# bms3_1.net
KiCad netlist of a schematic drawn in EAGLE
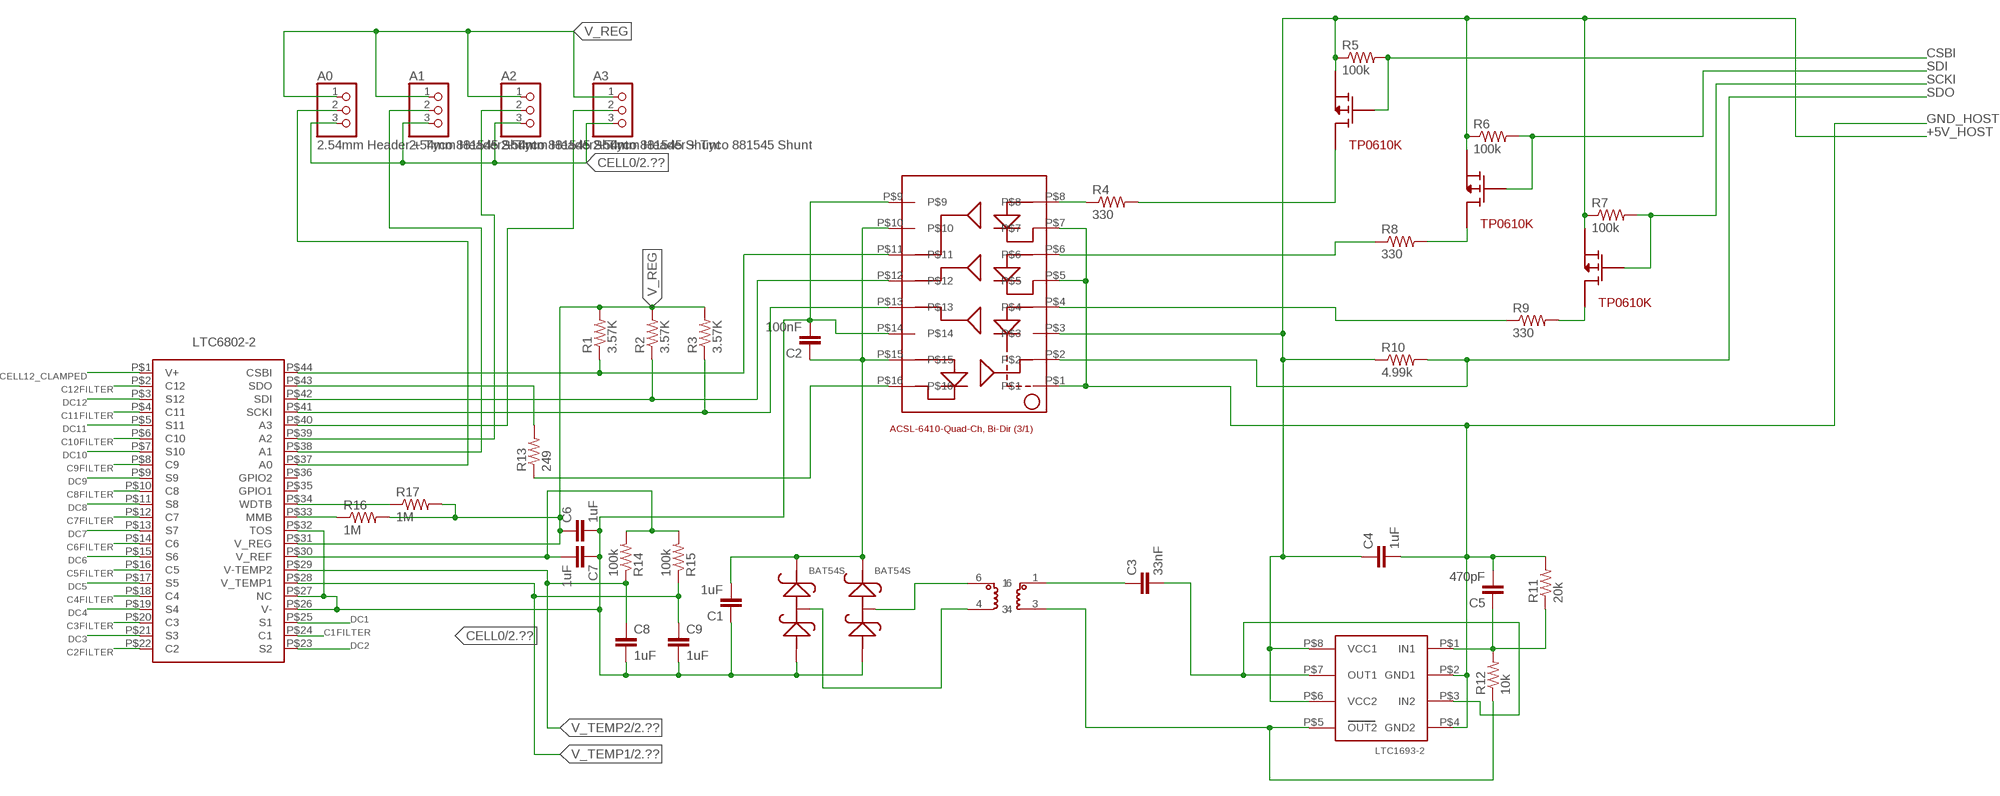
[diagram p0: schematic, sheet 1]
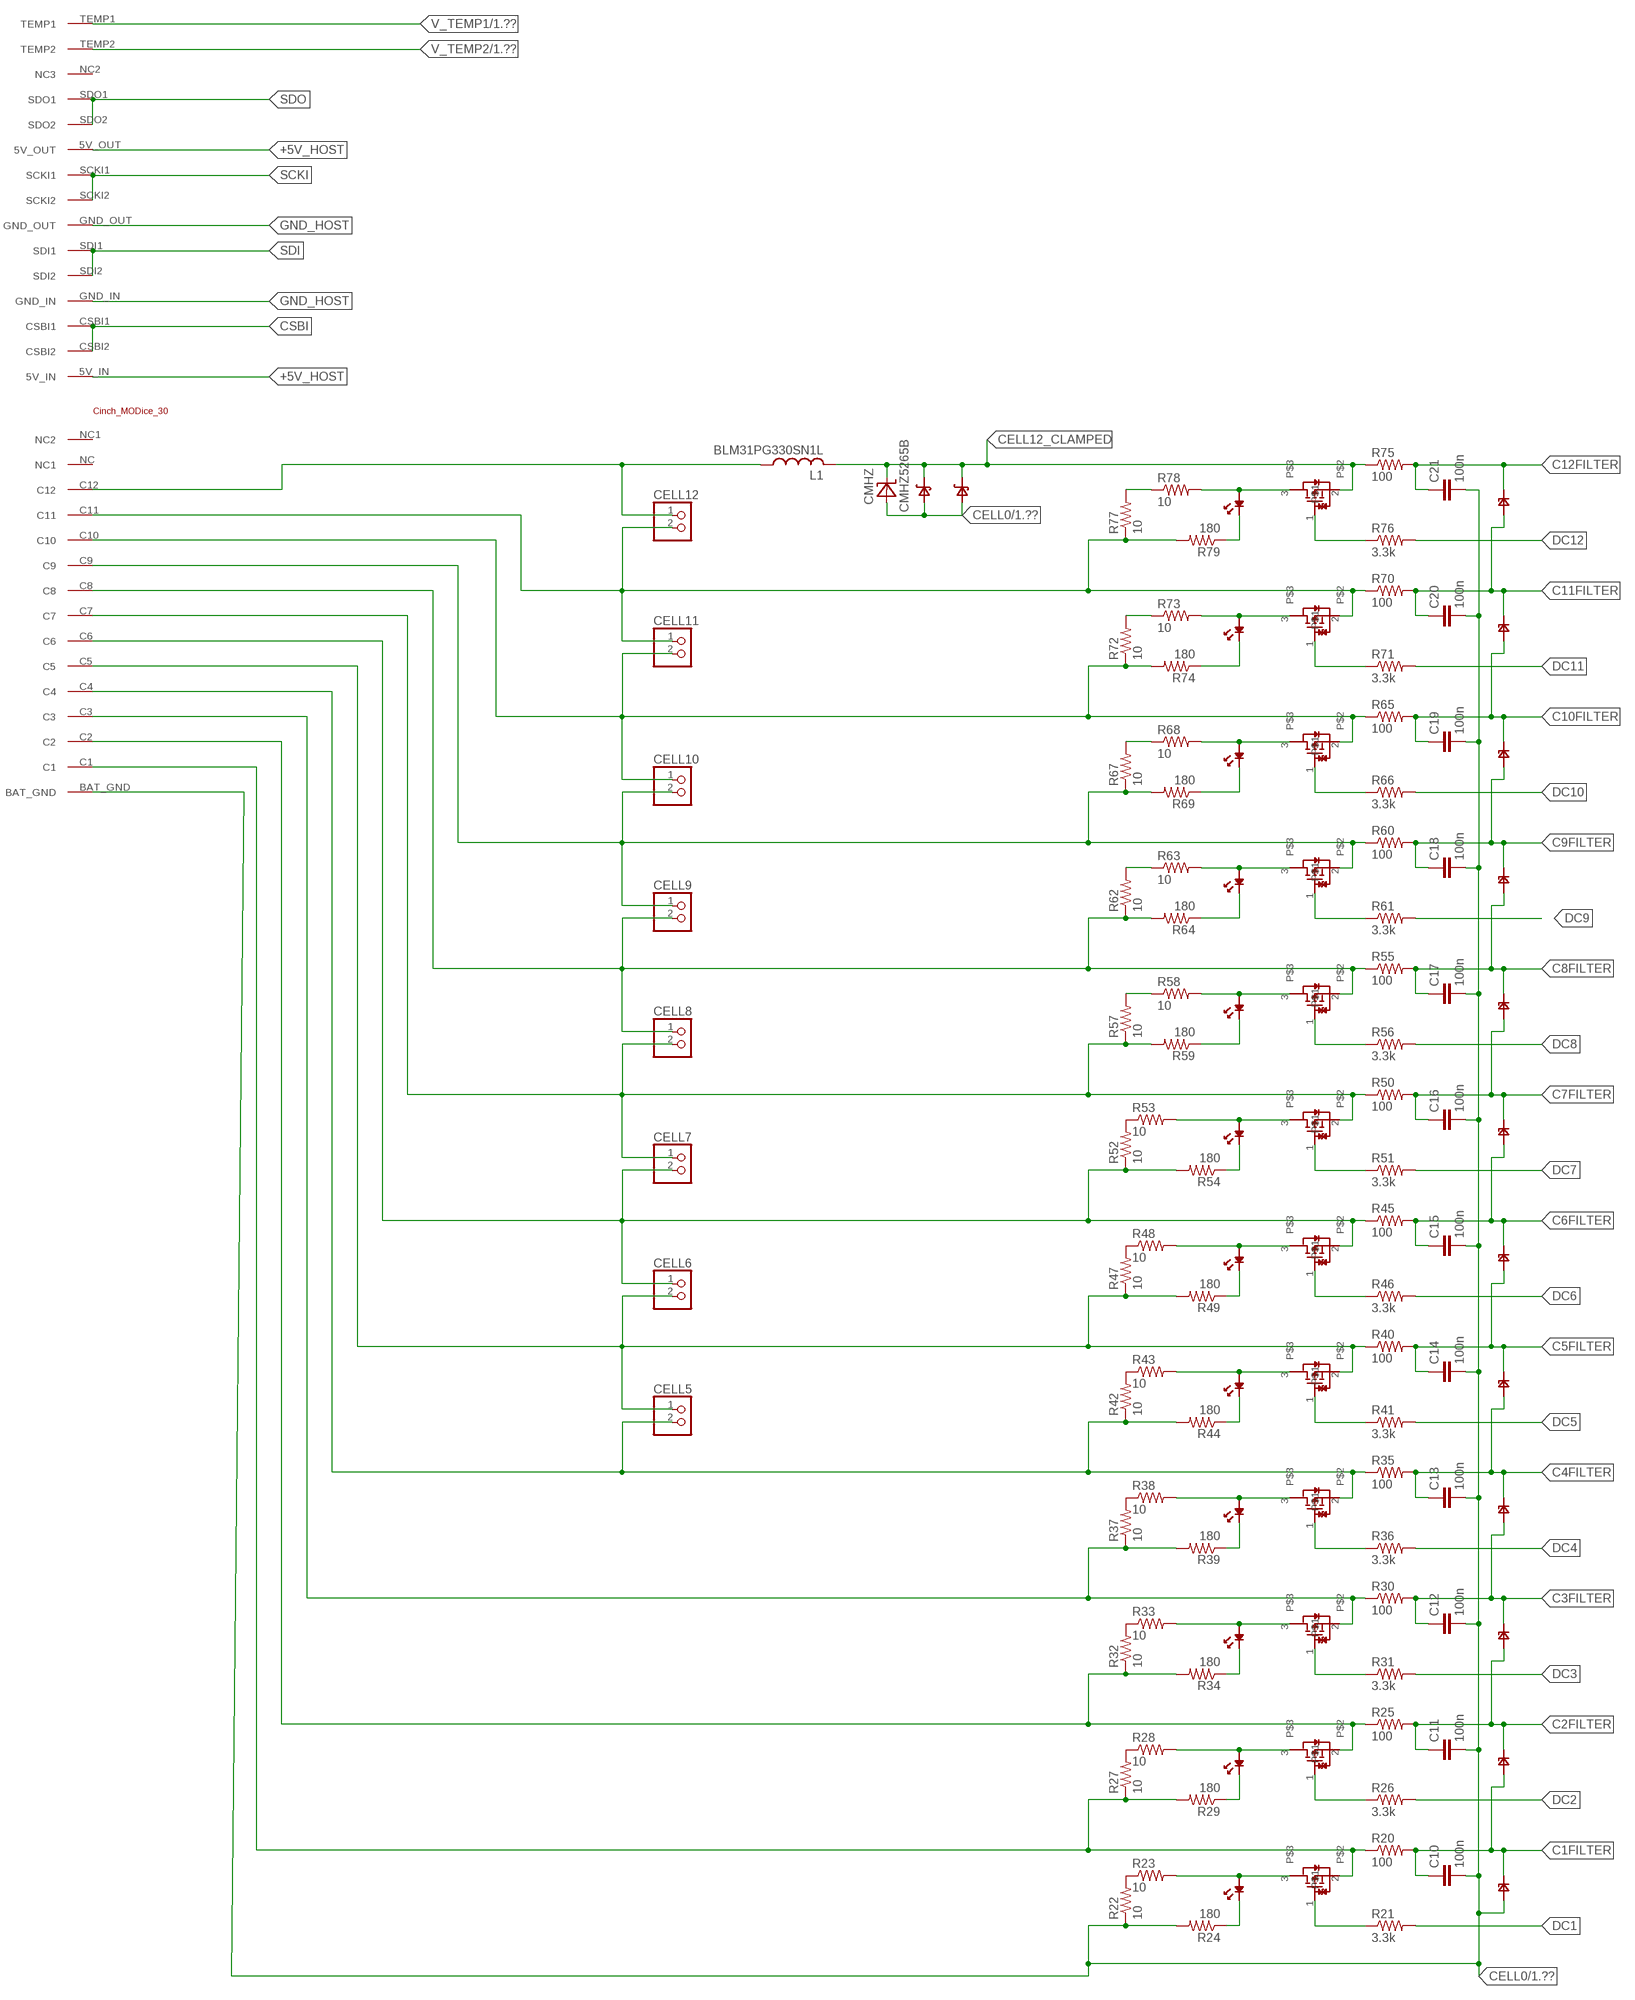
[diagram p1: schematic, sheet 2]

(export (version "E")
  (design (tool "Eeschema 10.0.6"))
  (components
    (comp (ref "BAT3")
      (value "BAT46W")
      (footprint "eagle-import:SOD123")
      (libsource (lib "eagle-import") (part "BAT46W"))
    )
    (comp (ref "BAT4")
      (value "BAT46W")
      (footprint "eagle-import:SOD123")
      (libsource (lib "eagle-import") (part "BAT46W"))
    )
    (comp (ref "C10")
      (value "100n")
      (footprint "eagle-import:C0603")
      (libsource (lib "eagle-import") (part "C-EUC0603"))
    )
    (comp (ref "C11")
      (value "100n")
      (footprint "eagle-import:C0603")
      (libsource (lib "eagle-import") (part "C-EUC0603"))
    )
    (comp (ref "C12")
      (value "100n")
      (footprint "eagle-import:C0603")
      (libsource (lib "eagle-import") (part "C-EUC0603"))
    )
    (comp (ref "C13")
      (value "100n")
      (footprint "eagle-import:C0603")
      (libsource (lib "eagle-import") (part "C-EUC0603"))
    )
    (comp (ref "C14")
      (value "100n")
      (footprint "eagle-import:C0603")
      (libsource (lib "eagle-import") (part "C-EUC0603"))
    )
    (comp (ref "C15")
      (value "100n")
      (footprint "eagle-import:C0603")
      (libsource (lib "eagle-import") (part "C-EUC0603"))
    )
    (comp (ref "C16")
      (value "100n")
      (footprint "eagle-import:C0603")
      (libsource (lib "eagle-import") (part "C-EUC0603"))
    )
    (comp (ref "C17")
      (value "100n")
      (footprint "eagle-import:C0603")
      (libsource (lib "eagle-import") (part "C-EUC0603"))
    )
    (comp (ref "C18")
      (value "100n")
      (footprint "eagle-import:C0603")
      (libsource (lib "eagle-import") (part "C-EUC0603"))
    )
    (comp (ref "C19")
      (value "100n")
      (footprint "eagle-import:C0603")
      (libsource (lib "eagle-import") (part "C-EUC0603"))
    )
    (comp (ref "C20")
      (value "100n")
      (footprint "eagle-import:C0603")
      (libsource (lib "eagle-import") (part "C-EUC0603"))
    )
    (comp (ref "C21")
      (value "100n")
      (footprint "eagle-import:C0603")
      (libsource (lib "eagle-import") (part "C-EUC0603"))
    )
    (comp (ref "CELL5")
      (value "PINHD-1X2")
      (footprint "eagle-import:1X02")
      (libsource (lib "eagle-import") (part "PINHD-1X2"))
    )
    (comp (ref "CELL6")
      (value "PINHD-1X2")
      (footprint "eagle-import:1X02")
      (libsource (lib "eagle-import") (part "PINHD-1X2"))
    )
    (comp (ref "CELL7")
      (value "PINHD-1X2")
      (footprint "eagle-import:1X02")
      (libsource (lib "eagle-import") (part "PINHD-1X2"))
    )
    (comp (ref "CELL8")
      (value "PINHD-1X2")
      (footprint "eagle-import:1X02")
      (libsource (lib "eagle-import") (part "PINHD-1X2"))
    )
    (comp (ref "CELL9")
      (value "PINHD-1X2")
      (footprint "eagle-import:1X02")
      (libsource (lib "eagle-import") (part "PINHD-1X2"))
    )
    (comp (ref "CELL10")
      (value "PINHD-1X2")
      (footprint "eagle-import:1X02")
      (libsource (lib "eagle-import") (part "PINHD-1X2"))
    )
    (comp (ref "CELL11")
      (value "PINHD-1X2")
      (footprint "eagle-import:1X02")
      (libsource (lib "eagle-import") (part "PINHD-1X2"))
    )
    (comp (ref "CELL12")
      (value "PINHD-1X2")
      (footprint "eagle-import:1X02")
      (libsource (lib "eagle-import") (part "PINHD-1X2"))
    )
    (comp (ref "CMHZ")
      (value "CMHZ5265B")
      (footprint "eagle-import:SOD123")
      (libsource (lib "eagle-import") (part "CMHZ5265B"))
    )
    (comp (ref "L1")
      (value "BLM31PG330SN1L")
      (footprint "eagle-import:L3216C")
      (libsource (lib "eagle-import") (part "L-USL3216C"))
    )
    (comp (ref "LED1")
      (value "LED-0805")
      (footprint "eagle-import:0805")
      (libsource (lib "eagle-import") (part "LED-0805"))
    )
    (comp (ref "LED2")
      (value "LED-0805")
      (footprint "eagle-import:0805")
      (libsource (lib "eagle-import") (part "LED-0805"))
    )
    (comp (ref "LED3")
      (value "LED-0805")
      (footprint "eagle-import:0805")
      (libsource (lib "eagle-import") (part "LED-0805"))
    )
    (comp (ref "LED4")
      (value "LED-0805")
      (footprint "eagle-import:0805")
      (libsource (lib "eagle-import") (part "LED-0805"))
    )
    (comp (ref "LED5")
      (value "LED-0805")
      (footprint "eagle-import:0805")
      (libsource (lib "eagle-import") (part "LED-0805"))
    )
    (comp (ref "LED6")
      (value "LED-0805")
      (footprint "eagle-import:0805")
      (libsource (lib "eagle-import") (part "LED-0805"))
    )
    (comp (ref "LED7")
      (value "LED-0805")
      (footprint "eagle-import:0805")
      (libsource (lib "eagle-import") (part "LED-0805"))
    )
    (comp (ref "LED8")
      (value "LED-0805")
      (footprint "eagle-import:0805")
      (libsource (lib "eagle-import") (part "LED-0805"))
    )
    (comp (ref "LED9")
      (value "LED-0805")
      (footprint "eagle-import:0805")
      (libsource (lib "eagle-import") (part "LED-0805"))
    )
    (comp (ref "LED10")
      (value "LED-0805")
      (footprint "eagle-import:0805")
      (libsource (lib "eagle-import") (part "LED-0805"))
    )
    (comp (ref "LED11")
      (value "LED-0805")
      (footprint "eagle-import:0805")
      (libsource (lib "eagle-import") (part "LED-0805"))
    )
    (comp (ref "LED12")
      (value "LED-0805")
      (footprint "eagle-import:0805")
      (libsource (lib "eagle-import") (part "LED-0805"))
    )
    (comp (ref "MODICE")
      (value "MODICE_30")
      (footprint "eagle-import:CINCH_HEADER30")
      (libsource (lib "eagle-import") (part "MODICE_30"))
    )
    (comp (ref "PD1")
      (value "PDZ7.5B")
      (footprint "eagle-import:SOD323")
      (libsource (lib "eagle-import") (part "PDZ7.5B"))
    )
    (comp (ref "PD2")
      (value "PDZ7.5B")
      (footprint "eagle-import:SOD323")
      (libsource (lib "eagle-import") (part "PDZ7.5B"))
    )
    (comp (ref "PD3")
      (value "PDZ7.5B")
      (footprint "eagle-import:SOD323")
      (libsource (lib "eagle-import") (part "PDZ7.5B"))
    )
    (comp (ref "PD4")
      (value "PDZ7.5B")
      (footprint "eagle-import:SOD323")
      (libsource (lib "eagle-import") (part "PDZ7.5B"))
    )
    (comp (ref "PD5")
      (value "PDZ7.5B")
      (footprint "eagle-import:SOD323")
      (libsource (lib "eagle-import") (part "PDZ7.5B"))
    )
    (comp (ref "PD6")
      (value "PDZ7.5B")
      (footprint "eagle-import:SOD323")
      (libsource (lib "eagle-import") (part "PDZ7.5B"))
    )
    (comp (ref "PD7")
      (value "PDZ7.5B")
      (footprint "eagle-import:SOD323")
      (libsource (lib "eagle-import") (part "PDZ7.5B"))
    )
    (comp (ref "PD8")
      (value "PDZ7.5B")
      (footprint "eagle-import:SOD323")
      (libsource (lib "eagle-import") (part "PDZ7.5B"))
    )
    (comp (ref "PD9")
      (value "PDZ7.5B")
      (footprint "eagle-import:SOD323")
      (libsource (lib "eagle-import") (part "PDZ7.5B"))
    )
    (comp (ref "PD10")
      (value "PDZ7.5B")
      (footprint "eagle-import:SOD323")
      (libsource (lib "eagle-import") (part "PDZ7.5B"))
    )
    (comp (ref "PD11")
      (value "PDZ7.5B")
      (footprint "eagle-import:SOD323")
      (libsource (lib "eagle-import") (part "PDZ7.5B"))
    )
    (comp (ref "PD12")
      (value "PDZ7.5B")
      (footprint "eagle-import:SOD323")
      (libsource (lib "eagle-import") (part "PDZ7.5B"))
    )
    (comp (ref "R20")
      (value "100")
      (footprint "eagle-import:R0603")
      (libsource (lib "eagle-import") (part "R-US_R0603"))
    )
    (comp (ref "R21")
      (value "3.3k")
      (footprint "eagle-import:R0603")
      (libsource (lib "eagle-import") (part "R-US_R0603"))
    )
    (comp (ref "R22")
      (value "10")
      (footprint "eagle-import:R2512")
      (libsource (lib "eagle-import") (part "R-US_R2512"))
    )
    (comp (ref "R23")
      (value "10")
      (footprint "eagle-import:R2512")
      (libsource (lib "eagle-import") (part "R-US_R2512"))
    )
    (comp (ref "R24")
      (value "180")
      (footprint "eagle-import:R0805")
      (libsource (lib "eagle-import") (part "R-US_R0805"))
    )
    (comp (ref "R25")
      (value "100")
      (footprint "eagle-import:R0603")
      (libsource (lib "eagle-import") (part "R-US_R0603"))
    )
    (comp (ref "R26")
      (value "3.3k")
      (footprint "eagle-import:R0603")
      (libsource (lib "eagle-import") (part "R-US_R0603"))
    )
    (comp (ref "R27")
      (value "10")
      (footprint "eagle-import:R2512")
      (libsource (lib "eagle-import") (part "R-US_R2512"))
    )
    (comp (ref "R28")
      (value "10")
      (footprint "eagle-import:R2512")
      (libsource (lib "eagle-import") (part "R-US_R2512"))
    )
    (comp (ref "R29")
      (value "180")
      (footprint "eagle-import:R0805")
      (libsource (lib "eagle-import") (part "R-US_R0805"))
    )
    (comp (ref "R30")
      (value "100")
      (footprint "eagle-import:R0603")
      (libsource (lib "eagle-import") (part "R-US_R0603"))
    )
    (comp (ref "R31")
      (value "3.3k")
      (footprint "eagle-import:R0603")
      (libsource (lib "eagle-import") (part "R-US_R0603"))
    )
    (comp (ref "R32")
      (value "10")
      (footprint "eagle-import:R2512")
      (libsource (lib "eagle-import") (part "R-US_R2512"))
    )
    (comp (ref "R33")
      (value "10")
      (footprint "eagle-import:R2512")
      (libsource (lib "eagle-import") (part "R-US_R2512"))
    )
    (comp (ref "R34")
      (value "180")
      (footprint "eagle-import:R0805")
      (libsource (lib "eagle-import") (part "R-US_R0805"))
    )
    (comp (ref "R35")
      (value "100")
      (footprint "eagle-import:R0603")
      (libsource (lib "eagle-import") (part "R-US_R0603"))
    )
    (comp (ref "R36")
      (value "3.3k")
      (footprint "eagle-import:R0603")
      (libsource (lib "eagle-import") (part "R-US_R0603"))
    )
    (comp (ref "R37")
      (value "10")
      (footprint "eagle-import:R2512")
      (libsource (lib "eagle-import") (part "R-US_R2512"))
    )
    (comp (ref "R38")
      (value "10")
      (footprint "eagle-import:R2512")
      (libsource (lib "eagle-import") (part "R-US_R2512"))
    )
    (comp (ref "R39")
      (value "180")
      (footprint "eagle-import:R0805")
      (libsource (lib "eagle-import") (part "R-US_R0805"))
    )
    (comp (ref "R40")
      (value "100")
      (footprint "eagle-import:R0603")
      (libsource (lib "eagle-import") (part "R-US_R0603"))
    )
    (comp (ref "R41")
      (value "3.3k")
      (footprint "eagle-import:R0603")
      (libsource (lib "eagle-import") (part "R-US_R0603"))
    )
    (comp (ref "R42")
      (value "10")
      (footprint "eagle-import:R2512")
      (libsource (lib "eagle-import") (part "R-US_R2512"))
    )
    (comp (ref "R43")
      (value "10")
      (footprint "eagle-import:R2512")
      (libsource (lib "eagle-import") (part "R-US_R2512"))
    )
    (comp (ref "R44")
      (value "180")
      (footprint "eagle-import:R0805")
      (libsource (lib "eagle-import") (part "R-US_R0805"))
    )
    (comp (ref "R45")
      (value "100")
      (footprint "eagle-import:R0603")
      (libsource (lib "eagle-import") (part "R-US_R0603"))
    )
    (comp (ref "R46")
      (value "3.3k")
      (footprint "eagle-import:R0603")
      (libsource (lib "eagle-import") (part "R-US_R0603"))
    )
    (comp (ref "R47")
      (value "10")
      (footprint "eagle-import:R2512")
      (libsource (lib "eagle-import") (part "R-US_R2512"))
    )
    (comp (ref "R48")
      (value "10")
      (footprint "eagle-import:R2512")
      (libsource (lib "eagle-import") (part "R-US_R2512"))
    )
    (comp (ref "R49")
      (value "180")
      (footprint "eagle-import:R0805")
      (libsource (lib "eagle-import") (part "R-US_R0805"))
    )
    (comp (ref "R50")
      (value "100")
      (footprint "eagle-import:R0603")
      (libsource (lib "eagle-import") (part "R-US_R0603"))
    )
    (comp (ref "R51")
      (value "3.3k")
      (footprint "eagle-import:R0603")
      (libsource (lib "eagle-import") (part "R-US_R0603"))
    )
    (comp (ref "R52")
      (value "10")
      (footprint "eagle-import:R2512")
      (libsource (lib "eagle-import") (part "R-US_R2512"))
    )
    (comp (ref "R53")
      (value "10")
      (footprint "eagle-import:R2512")
      (libsource (lib "eagle-import") (part "R-US_R2512"))
    )
    (comp (ref "R54")
      (value "180")
      (footprint "eagle-import:R0805")
      (libsource (lib "eagle-import") (part "R-US_R0805"))
    )
    (comp (ref "R55")
      (value "100")
      (footprint "eagle-import:R0603")
      (libsource (lib "eagle-import") (part "R-US_R0603"))
    )
    (comp (ref "R56")
      (value "3.3k")
      (footprint "eagle-import:R0603")
      (libsource (lib "eagle-import") (part "R-US_R0603"))
    )
    (comp (ref "R57")
      (value "10")
      (footprint "eagle-import:R2512")
      (libsource (lib "eagle-import") (part "R-US_R2512"))
    )
    (comp (ref "R58")
      (value "10")
      (footprint "eagle-import:R2512")
      (libsource (lib "eagle-import") (part "R-US_R2512"))
    )
    (comp (ref "R59")
      (value "180")
      (footprint "eagle-import:R0805")
      (libsource (lib "eagle-import") (part "R-US_R0805"))
    )
    (comp (ref "R60")
      (value "100")
      (footprint "eagle-import:R0603")
      (libsource (lib "eagle-import") (part "R-US_R0603"))
    )
    (comp (ref "R61")
      (value "3.3k")
      (footprint "eagle-import:R0603")
      (libsource (lib "eagle-import") (part "R-US_R0603"))
    )
    (comp (ref "R62")
      (value "10")
      (footprint "eagle-import:R2512")
      (libsource (lib "eagle-import") (part "R-US_R2512"))
    )
    (comp (ref "R63")
      (value "10")
      (footprint "eagle-import:R2512")
      (libsource (lib "eagle-import") (part "R-US_R2512"))
    )
    (comp (ref "R64")
      (value "180")
      (footprint "eagle-import:R0805")
      (libsource (lib "eagle-import") (part "R-US_R0805"))
    )
    (comp (ref "R65")
      (value "100")
      (footprint "eagle-import:R0603")
      (libsource (lib "eagle-import") (part "R-US_R0603"))
    )
    (comp (ref "R66")
      (value "3.3k")
      (footprint "eagle-import:R0603")
      (libsource (lib "eagle-import") (part "R-US_R0603"))
    )
    (comp (ref "R67")
      (value "10")
      (footprint "eagle-import:R2512")
      (libsource (lib "eagle-import") (part "R-US_R2512"))
    )
    (comp (ref "R68")
      (value "10")
      (footprint "eagle-import:R2512")
      (libsource (lib "eagle-import") (part "R-US_R2512"))
    )
    (comp (ref "R69")
      (value "180")
      (footprint "eagle-import:R0805")
      (libsource (lib "eagle-import") (part "R-US_R0805"))
    )
    (comp (ref "R70")
      (value "100")
      (footprint "eagle-import:R0603")
      (libsource (lib "eagle-import") (part "R-US_R0603"))
    )
    (comp (ref "R71")
      (value "3.3k")
      (footprint "eagle-import:R0603")
      (libsource (lib "eagle-import") (part "R-US_R0603"))
    )
    (comp (ref "R72")
      (value "10")
      (footprint "eagle-import:R2512")
      (libsource (lib "eagle-import") (part "R-US_R2512"))
    )
    (comp (ref "R73")
      (value "10")
      (footprint "eagle-import:R2512")
      (libsource (lib "eagle-import") (part "R-US_R2512"))
    )
    (comp (ref "R74")
      (value "180")
      (footprint "eagle-import:R0805")
      (libsource (lib "eagle-import") (part "R-US_R0805"))
    )
    (comp (ref "R75")
      (value "100")
      (footprint "eagle-import:R0603")
      (libsource (lib "eagle-import") (part "R-US_R0603"))
    )
    (comp (ref "R76")
      (value "3.3k")
      (footprint "eagle-import:R0603")
      (libsource (lib "eagle-import") (part "R-US_R0603"))
    )
    (comp (ref "R77")
      (value "10")
      (footprint "eagle-import:R2512")
      (libsource (lib "eagle-import") (part "R-US_R2512"))
    )
    (comp (ref "R78")
      (value "10")
      (footprint "eagle-import:R2512")
      (libsource (lib "eagle-import") (part "R-US_R2512"))
    )
    (comp (ref "R79")
      (value "180")
      (footprint "eagle-import:R0805")
      (libsource (lib "eagle-import") (part "R-US_R0805"))
    )
    (comp (ref "T1")
      (value "RTR020P02")
      (footprint "eagle-import:TSMT3")
      (libsource (lib "eagle-import") (part "RTR020P02"))
    )
    (comp (ref "T2")
      (value "RTR020P02")
      (footprint "eagle-import:TSMT3")
      (libsource (lib "eagle-import") (part "RTR020P02"))
    )
    (comp (ref "T3")
      (value "RTR020P02")
      (footprint "eagle-import:TSMT3")
      (libsource (lib "eagle-import") (part "RTR020P02"))
    )
    (comp (ref "T4")
      (value "RTR020P02")
      (footprint "eagle-import:TSMT3")
      (libsource (lib "eagle-import") (part "RTR020P02"))
    )
    (comp (ref "T5")
      (value "RTR020P02")
      (footprint "eagle-import:TSMT3")
      (libsource (lib "eagle-import") (part "RTR020P02"))
    )
    (comp (ref "T6")
      (value "RTR020P02")
      (footprint "eagle-import:TSMT3")
      (libsource (lib "eagle-import") (part "RTR020P02"))
    )
    (comp (ref "T7")
      (value "RTR020P02")
      (footprint "eagle-import:TSMT3")
      (libsource (lib "eagle-import") (part "RTR020P02"))
    )
    (comp (ref "T8")
      (value "RTR020P02")
      (footprint "eagle-import:TSMT3")
      (libsource (lib "eagle-import") (part "RTR020P02"))
    )
    (comp (ref "T9")
      (value "RTR020P02")
      (footprint "eagle-import:TSMT3")
      (libsource (lib "eagle-import") (part "RTR020P02"))
    )
    (comp (ref "T10")
      (value "RTR020P02")
      (footprint "eagle-import:TSMT3")
      (libsource (lib "eagle-import") (part "RTR020P02"))
    )
    (comp (ref "T11")
      (value "RTR020P02")
      (footprint "eagle-import:TSMT3")
      (libsource (lib "eagle-import") (part "RTR020P02"))
    )
    (comp (ref "T12")
      (value "RTR020P02")
      (footprint "eagle-import:TSMT3")
      (libsource (lib "eagle-import") (part "RTR020P02"))
    )
    (comp (ref "A0")
      (value "2.54mm Header + Tyco 881545 Shunt")
      (footprint "eagle-import:1X03")
      (libsource (lib "eagle-import") (part "PINHD-1X3"))
    )
    (comp (ref "A1")
      (value "2.54mm Header + Tyco 881545 Shunt")
      (footprint "eagle-import:1X03")
      (libsource (lib "eagle-import") (part "PINHD-1X3"))
    )
    (comp (ref "A2")
      (value "2.54mm Header + Tyco 881545 Shunt")
      (footprint "eagle-import:1X03")
      (libsource (lib "eagle-import") (part "PINHD-1X3"))
    )
    (comp (ref "A3")
      (value "2.54mm Header + Tyco 881545 Shunt")
      (footprint "eagle-import:1X03")
      (libsource (lib "eagle-import") (part "PINHD-1X3"))
    )
    (comp (ref "ACSL6410")
      (value "ACSL-6410")
      (footprint "eagle-import:ACSL-6410-SO16")
      (libsource (lib "eagle-import") (part "ACSL-6410"))
    )
    (comp (ref "BAT1")
      (value "BAT54S")
      (footprint "eagle-import:SOT-23")
      (libsource (lib "eagle-import") (part "BAT54S"))
    )
    (comp (ref "BAT2")
      (value "BAT54S")
      (footprint "eagle-import:SOT-23")
      (libsource (lib "eagle-import") (part "BAT54S"))
    )
    (comp (ref "C1")
      (value "1uF")
      (footprint "eagle-import:C0603")
      (libsource (lib "eagle-import") (part "C-EUC0603"))
    )
    (comp (ref "C2")
      (value "100nF")
      (footprint "eagle-import:C0603")
      (libsource (lib "eagle-import") (part "C-EUC0603"))
    )
    (comp (ref "C3")
      (value "33nF")
      (footprint "eagle-import:C0603")
      (libsource (lib "eagle-import") (part "C-EUC0603"))
    )
    (comp (ref "C4")
      (value "1uF")
      (footprint "eagle-import:C0603")
      (libsource (lib "eagle-import") (part "C-EUC0603"))
    )
    (comp (ref "C5")
      (value "470pF")
      (footprint "eagle-import:C0603")
      (libsource (lib "eagle-import") (part "C-EUC0603"))
    )
    (comp (ref "C6")
      (value "1uF")
      (footprint "eagle-import:C0603")
      (libsource (lib "eagle-import") (part "C-EUC0603"))
    )
    (comp (ref "C7")
      (value "1uF")
      (footprint "eagle-import:C0603")
      (libsource (lib "eagle-import") (part "C-EUC0603"))
    )
    (comp (ref "C8")
      (value "1uF")
      (footprint "eagle-import:C0603")
      (libsource (lib "eagle-import") (part "C-EUC0603"))
    )
    (comp (ref "C9")
      (value "1uF")
      (footprint "eagle-import:C0603")
      (libsource (lib "eagle-import") (part "C-EUC0603"))
    )
    (comp (ref "CSBI")
      (value "TP0610K")
      (footprint "eagle-import:SOT-23")
      (libsource (lib "eagle-import") (part "TP0610K"))
    )
    (comp (ref "LTC1693")
      (value "LTC1693-2")
      (footprint "eagle-import:S8-LTC1693-2")
      (libsource (lib "eagle-import") (part "LTC1693-2"))
    )
    (comp (ref "PE68386")
      (value "PE68386")
      (footprint "eagle-import:PE68386")
      (libsource (lib "eagle-import") (part "PE68386"))
    )
    (comp (ref "R1")
      (value "3.57K")
      (footprint "eagle-import:R0603")
      (libsource (lib "eagle-import") (part "R-US_R0603"))
    )
    (comp (ref "R2")
      (value "3.57K")
      (footprint "eagle-import:R0603")
      (libsource (lib "eagle-import") (part "R-US_R0603"))
    )
    (comp (ref "R3")
      (value "3.57K")
      (footprint "eagle-import:R0603")
      (libsource (lib "eagle-import") (part "R-US_R0603"))
    )
    (comp (ref "R4")
      (value "330")
      (footprint "eagle-import:R0603")
      (libsource (lib "eagle-import") (part "R-US_R0603"))
    )
    (comp (ref "R5")
      (value "100k")
      (footprint "eagle-import:R0603")
      (libsource (lib "eagle-import") (part "R-US_R0603"))
    )
    (comp (ref "R6")
      (value "100k")
      (footprint "eagle-import:R0603")
      (libsource (lib "eagle-import") (part "R-US_R0603"))
    )
    (comp (ref "R7")
      (value "100k")
      (footprint "eagle-import:R0603")
      (libsource (lib "eagle-import") (part "R-US_R0603"))
    )
    (comp (ref "R8")
      (value "330")
      (footprint "eagle-import:R0603")
      (libsource (lib "eagle-import") (part "R-US_R0603"))
    )
    (comp (ref "R9")
      (value "330")
      (footprint "eagle-import:R0603")
      (libsource (lib "eagle-import") (part "R-US_R0603"))
    )
    (comp (ref "R10")
      (value "4.99k")
      (footprint "eagle-import:R0603")
      (libsource (lib "eagle-import") (part "R-US_R0603"))
    )
    (comp (ref "R11")
      (value "20k")
      (footprint "eagle-import:R0603")
      (libsource (lib "eagle-import") (part "R-US_R0603"))
    )
    (comp (ref "R12")
      (value "10k")
      (footprint "eagle-import:R0603")
      (libsource (lib "eagle-import") (part "R-US_R0603"))
    )
    (comp (ref "R13")
      (value "249")
      (footprint "eagle-import:R0603")
      (libsource (lib "eagle-import") (part "R-US_R0603"))
    )
    (comp (ref "R14")
      (value "100k")
      (footprint "eagle-import:R0603")
      (libsource (lib "eagle-import") (part "R-US_R0603"))
    )
    (comp (ref "R15")
      (value "100k")
      (footprint "eagle-import:R0603")
      (libsource (lib "eagle-import") (part "R-US_R0603"))
    )
    (comp (ref "R16")
      (value "1M")
      (footprint "eagle-import:R0603")
      (libsource (lib "eagle-import") (part "R-US_R0603"))
    )
    (comp (ref "R17")
      (value "1M")
      (footprint "eagle-import:R0603")
      (libsource (lib "eagle-import") (part "R-US_R0603"))
    )
    (comp (ref "SCKI")
      (value "TP0610K")
      (footprint "eagle-import:SOT-23")
      (libsource (lib "eagle-import") (part "TP0610K"))
    )
    (comp (ref "SDI")
      (value "TP0610K")
      (footprint "eagle-import:SOT-23")
      (libsource (lib "eagle-import") (part "TP0610K"))
    )
    (comp (ref "X-BMS")
      (value "LTC6802-2")
      (footprint "eagle-import:SSOP-44")
      (libsource (lib "eagle-import") (part "LTC6802-2"))
    )
  )
  (nets
    (net (code "1") (name "+5V_HOST") (class "Default")
      (node (ref "ACSL6410") (pin "P$3") (pinfunction "P$3_P$3") (pintype "bidirectional"))
      (node (ref "C4") (pin "1") (pinfunction "1_1") (pintype "passive"))
      (node (ref "CSBI") (pin "2") (pinfunction "P$2_2") (pintype "bidirectional"))
      (node (ref "LTC1693") (pin "P$6") (pinfunction "VCC2_P$6") (pintype "bidirectional"))
      (node (ref "LTC1693") (pin "P$8") (pinfunction "VCC1_P$8") (pintype "bidirectional"))
      (node (ref "MODICE") (pin "5V_IN") (pinfunction "5V_IN_5V_IN") (pintype "bidirectional"))
      (node (ref "MODICE") (pin "5V_OUT") (pinfunction "5V_OUT_5V_OUT") (pintype "bidirectional"))
      (node (ref "R10") (pin "1") (pinfunction "1_1") (pintype "passive"))
      (node (ref "R5") (pin "1") (pinfunction "1_1") (pintype "passive"))
      (node (ref "R6") (pin "1") (pinfunction "1_1") (pintype "passive"))
      (node (ref "R7") (pin "1") (pinfunction "1_1") (pintype "passive"))
      (node (ref "SCKI") (pin "2") (pinfunction "P$2_2") (pintype "bidirectional"))
      (node (ref "SDI") (pin "2") (pinfunction "P$2_2") (pintype "bidirectional"))
    )
    (net (code "2") (name "C1FILTER") (class "Default")
      (node (ref "C10") (pin "1") (pinfunction "1_1") (pintype "passive"))
      (node (ref "PD1") (pin "P$1") (pinfunction "P$1_P$1") (pintype "passive"))
      (node (ref "PD2") (pin "P$2") (pinfunction "P$2_P$2") (pintype "passive"))
      (node (ref "R20") (pin "2") (pinfunction "2_2") (pintype "passive"))
      (node (ref "X-BMS") (pin "P$24") (pinfunction "C1_P$24") (pintype "bidirectional"))
    )
    (net (code "3") (name "C2FILTER") (class "Default")
      (node (ref "C11") (pin "1") (pinfunction "1_1") (pintype "passive"))
      (node (ref "PD2") (pin "P$1") (pinfunction "P$1_P$1") (pintype "passive"))
      (node (ref "PD3") (pin "P$2") (pinfunction "P$2_P$2") (pintype "passive"))
      (node (ref "R25") (pin "2") (pinfunction "2_2") (pintype "passive"))
      (node (ref "X-BMS") (pin "P$22") (pinfunction "C2_P$22") (pintype "bidirectional"))
    )
    (net (code "4") (name "C3FILTER") (class "Default")
      (node (ref "C12") (pin "1") (pinfunction "1_1") (pintype "passive"))
      (node (ref "PD3") (pin "P$1") (pinfunction "P$1_P$1") (pintype "passive"))
      (node (ref "PD4") (pin "P$2") (pinfunction "P$2_P$2") (pintype "passive"))
      (node (ref "R30") (pin "2") (pinfunction "2_2") (pintype "passive"))
      (node (ref "X-BMS") (pin "P$20") (pinfunction "C3_P$20") (pintype "bidirectional"))
    )
    (net (code "5") (name "C4FILTER") (class "Default")
      (node (ref "C13") (pin "1") (pinfunction "1_1") (pintype "passive"))
      (node (ref "PD4") (pin "P$1") (pinfunction "P$1_P$1") (pintype "passive"))
      (node (ref "PD5") (pin "P$2") (pinfunction "P$2_P$2") (pintype "passive"))
      (node (ref "R35") (pin "2") (pinfunction "2_2") (pintype "passive"))
      (node (ref "X-BMS") (pin "P$18") (pinfunction "C4_P$18") (pintype "bidirectional"))
    )
    (net (code "6") (name "C5FILTER") (class "Default")
      (node (ref "C14") (pin "1") (pinfunction "1_1") (pintype "passive"))
      (node (ref "PD5") (pin "P$1") (pinfunction "P$1_P$1") (pintype "passive"))
      (node (ref "PD6") (pin "P$2") (pinfunction "P$2_P$2") (pintype "passive"))
      (node (ref "R40") (pin "2") (pinfunction "2_2") (pintype "passive"))
      (node (ref "X-BMS") (pin "P$16") (pinfunction "C5_P$16") (pintype "bidirectional"))
    )
    (net (code "7") (name "C6FILTER") (class "Default")
      (node (ref "C15") (pin "1") (pinfunction "1_1") (pintype "passive"))
      (node (ref "PD6") (pin "P$1") (pinfunction "P$1_P$1") (pintype "passive"))
      (node (ref "PD7") (pin "P$2") (pinfunction "P$2_P$2") (pintype "passive"))
      (node (ref "R45") (pin "2") (pinfunction "2_2") (pintype "passive"))
      (node (ref "X-BMS") (pin "P$14") (pinfunction "C6_P$14") (pintype "bidirectional"))
    )
    (net (code "8") (name "C7FILTER") (class "Default")
      (node (ref "C16") (pin "1") (pinfunction "1_1") (pintype "passive"))
      (node (ref "PD7") (pin "P$1") (pinfunction "P$1_P$1") (pintype "passive"))
      (node (ref "PD8") (pin "P$2") (pinfunction "P$2_P$2") (pintype "passive"))
      (node (ref "R50") (pin "2") (pinfunction "2_2") (pintype "passive"))
      (node (ref "X-BMS") (pin "P$12") (pinfunction "C7_P$12") (pintype "bidirectional"))
    )
    (net (code "9") (name "C8FILTER") (class "Default")
      (node (ref "C17") (pin "1") (pinfunction "1_1") (pintype "passive"))
      (node (ref "PD8") (pin "P$1") (pinfunction "P$1_P$1") (pintype "passive"))
      (node (ref "PD9") (pin "P$2") (pinfunction "P$2_P$2") (pintype "passive"))
      (node (ref "R55") (pin "2") (pinfunction "2_2") (pintype "passive"))
      (node (ref "X-BMS") (pin "P$10") (pinfunction "C8_P$10") (pintype "bidirectional"))
    )
    (net (code "10") (name "C9FILTER") (class "Default")
      (node (ref "C18") (pin "1") (pinfunction "1_1") (pintype "passive"))
      (node (ref "PD10") (pin "P$2") (pinfunction "P$2_P$2") (pintype "passive"))
      (node (ref "PD9") (pin "P$1") (pinfunction "P$1_P$1") (pintype "passive"))
      (node (ref "R60") (pin "2") (pinfunction "2_2") (pintype "passive"))
      (node (ref "X-BMS") (pin "P$8") (pinfunction "C9_P$8") (pintype "bidirectional"))
    )
    (net (code "11") (name "C10FILTER") (class "Default")
      (node (ref "C19") (pin "1") (pinfunction "1_1") (pintype "passive"))
      (node (ref "PD10") (pin "P$1") (pinfunction "P$1_P$1") (pintype "passive"))
      (node (ref "PD11") (pin "P$2") (pinfunction "P$2_P$2") (pintype "passive"))
      (node (ref "R65") (pin "2") (pinfunction "2_2") (pintype "passive"))
      (node (ref "X-BMS") (pin "P$6") (pinfunction "C10_P$6") (pintype "bidirectional"))
    )
    (net (code "12") (name "C11FILTER") (class "Default")
      (node (ref "C20") (pin "1") (pinfunction "1_1") (pintype "passive"))
      (node (ref "PD11") (pin "P$1") (pinfunction "P$1_P$1") (pintype "passive"))
      (node (ref "PD12") (pin "P$2") (pinfunction "P$2_P$2") (pintype "passive"))
      (node (ref "R70") (pin "2") (pinfunction "2_2") (pintype "passive"))
      (node (ref "X-BMS") (pin "P$4") (pinfunction "C11_P$4") (pintype "bidirectional"))
    )
    (net (code "13") (name "C12FILTER") (class "Default")
      (node (ref "C21") (pin "1") (pinfunction "1_1") (pintype "passive"))
      (node (ref "PD12") (pin "P$1") (pinfunction "P$1_P$1") (pintype "passive"))
      (node (ref "R75") (pin "2") (pinfunction "2_2") (pintype "passive"))
      (node (ref "X-BMS") (pin "P$2") (pinfunction "C12_P$2") (pintype "bidirectional"))
    )
    (net (code "14") (name "CELL0") (class "Default")
      (node (ref "A0") (pin "3") (pinfunction "3_3") (pintype "passive"))
      (node (ref "A1") (pin "3") (pinfunction "3_3") (pintype "passive"))
      (node (ref "A2") (pin "3") (pinfunction "3_3") (pintype "passive"))
      (node (ref "A3") (pin "3") (pinfunction "3_3") (pintype "passive"))
      (node (ref "ACSL6410") (pin "P$14") (pinfunction "P$14_P$14") (pintype "bidirectional"))
      (node (ref "ACSL6410") (pin "P$9") (pinfunction "P$9_P$9") (pintype "bidirectional"))
      (node (ref "BAT1") (pin "1") (pinfunction "1_1") (pintype "passive"))
      (node (ref "BAT2") (pin "1") (pinfunction "1_1") (pintype "passive"))
      (node (ref "BAT3") (pin "POS") (pinfunction "POS_POS") (pintype "passive"))
      (node (ref "BAT4") (pin "POS") (pinfunction "POS_POS") (pintype "passive"))
      (node (ref "C1") (pin "1") (pinfunction "1_1") (pintype "passive"))
      (node (ref "C10") (pin "2") (pinfunction "2_2") (pintype "passive"))
      (node (ref "C11") (pin "2") (pinfunction "2_2") (pintype "passive"))
      (node (ref "C12") (pin "2") (pinfunction "2_2") (pintype "passive"))
      (node (ref "C13") (pin "2") (pinfunction "2_2") (pintype "passive"))
      (node (ref "C14") (pin "2") (pinfunction "2_2") (pintype "passive"))
      (node (ref "C15") (pin "2") (pinfunction "2_2") (pintype "passive"))
      (node (ref "C16") (pin "2") (pinfunction "2_2") (pintype "passive"))
      (node (ref "C17") (pin "2") (pinfunction "2_2") (pintype "passive"))
      (node (ref "C18") (pin "2") (pinfunction "2_2") (pintype "passive"))
      (node (ref "C19") (pin "2") (pinfunction "2_2") (pintype "passive"))
      (node (ref "C2") (pin "2") (pinfunction "2_2") (pintype "passive"))
      (node (ref "C20") (pin "2") (pinfunction "2_2") (pintype "passive"))
      (node (ref "C21") (pin "2") (pinfunction "2_2") (pintype "passive"))
      (node (ref "C6") (pin "2") (pinfunction "2_2") (pintype "passive"))
      (node (ref "C7") (pin "1") (pinfunction "1_1") (pintype "passive"))
      (node (ref "C8") (pin "2") (pinfunction "2_2") (pintype "passive"))
      (node (ref "C9") (pin "2") (pinfunction "2_2") (pintype "passive"))
      (node (ref "CMHZ") (pin "POS") (pinfunction "A_POS") (pintype "passive"))
      (node (ref "MODICE") (pin "BAT_GND") (pinfunction "BAT_GND_BAT_GND") (pintype "bidirectional"))
      (node (ref "PD1") (pin "P$2") (pinfunction "P$2_P$2") (pintype "passive"))
      (node (ref "R22") (pin "1") (pinfunction "1_1") (pintype "passive"))
      (node (ref "R24") (pin "2") (pinfunction "2_2") (pintype "passive"))
      (node (ref "X-BMS") (pin "P$26") (pinfunction "V-_P$26") (pintype "bidirectional"))
      (node (ref "X-BMS") (pin "P$27") (pinfunction "NC_P$27") (pintype "bidirectional"))
      (node (ref "X-BMS") (pin "P$32") (pinfunction "TOS_P$32") (pintype "bidirectional"))
    )
    (net (code "15") (name "CELL12_CLAMPED") (class "Default")
      (node (ref "BAT3") (pin "NEG") (pinfunction "NEG_NEG") (pintype "passive"))
      (node (ref "BAT4") (pin "NEG") (pinfunction "NEG_NEG") (pintype "passive"))
      (node (ref "CMHZ") (pin "NEG") (pinfunction "C_NEG") (pintype "passive"))
      (node (ref "L1") (pin "2") (pinfunction "2_2") (pintype "passive"))
      (node (ref "R75") (pin "1") (pinfunction "1_1") (pintype "passive"))
      (node (ref "T12") (pin "2") (pinfunction "P$2_2") (pintype "passive"))
      (node (ref "X-BMS") (pin "P$1") (pinfunction "V+_P$1") (pintype "bidirectional"))
    )
    (net (code "16") (name "CSBI") (class "Default")
      (node (ref "CSBI") (pin "1") (pinfunction "P$1_1") (pintype "bidirectional"))
      (node (ref "MODICE") (pin "CSBI1") (pinfunction "CSBI1_CSBI1") (pintype "bidirectional"))
      (node (ref "MODICE") (pin "CSBI2") (pinfunction "CSBI2_CSBI2") (pintype "bidirectional"))
      (node (ref "R5") (pin "2") (pinfunction "2_2") (pintype "passive"))
    )
    (net (code "17") (name "DC1") (class "Default")
      (node (ref "R21") (pin "2") (pinfunction "2_2") (pintype "passive"))
      (node (ref "X-BMS") (pin "P$25") (pinfunction "S1_P$25") (pintype "bidirectional"))
    )
    (net (code "18") (name "DC2") (class "Default")
      (node (ref "R26") (pin "2") (pinfunction "2_2") (pintype "passive"))
      (node (ref "X-BMS") (pin "P$23") (pinfunction "S2_P$23") (pintype "bidirectional"))
    )
    (net (code "19") (name "DC3") (class "Default")
      (node (ref "R31") (pin "2") (pinfunction "2_2") (pintype "passive"))
      (node (ref "X-BMS") (pin "P$21") (pinfunction "S3_P$21") (pintype "bidirectional"))
    )
    (net (code "20") (name "DC4") (class "Default")
      (node (ref "R36") (pin "2") (pinfunction "2_2") (pintype "passive"))
      (node (ref "X-BMS") (pin "P$19") (pinfunction "S4_P$19") (pintype "bidirectional"))
    )
    (net (code "21") (name "DC5") (class "Default")
      (node (ref "R41") (pin "2") (pinfunction "2_2") (pintype "passive"))
      (node (ref "X-BMS") (pin "P$17") (pinfunction "S5_P$17") (pintype "bidirectional"))
    )
    (net (code "22") (name "DC6") (class "Default")
      (node (ref "R46") (pin "2") (pinfunction "2_2") (pintype "passive"))
      (node (ref "X-BMS") (pin "P$15") (pinfunction "S6_P$15") (pintype "bidirectional"))
    )
    (net (code "23") (name "DC7") (class "Default")
      (node (ref "R51") (pin "2") (pinfunction "2_2") (pintype "passive"))
      (node (ref "X-BMS") (pin "P$13") (pinfunction "S7_P$13") (pintype "bidirectional"))
    )
    (net (code "24") (name "DC8") (class "Default")
      (node (ref "R56") (pin "2") (pinfunction "2_2") (pintype "passive"))
      (node (ref "X-BMS") (pin "P$11") (pinfunction "S8_P$11") (pintype "bidirectional"))
    )
    (net (code "25") (name "DC9") (class "Default")
      (node (ref "R61") (pin "2") (pinfunction "2_2") (pintype "passive"))
      (node (ref "X-BMS") (pin "P$9") (pinfunction "S9_P$9") (pintype "bidirectional"))
    )
    (net (code "26") (name "DC10") (class "Default")
      (node (ref "R66") (pin "2") (pinfunction "2_2") (pintype "passive"))
      (node (ref "X-BMS") (pin "P$7") (pinfunction "S10_P$7") (pintype "bidirectional"))
    )
    (net (code "27") (name "DC11") (class "Default")
      (node (ref "R71") (pin "2") (pinfunction "2_2") (pintype "passive"))
      (node (ref "X-BMS") (pin "P$5") (pinfunction "S11_P$5") (pintype "bidirectional"))
    )
    (net (code "28") (name "DC12") (class "Default")
      (node (ref "R76") (pin "2") (pinfunction "2_2") (pintype "passive"))
      (node (ref "X-BMS") (pin "P$3") (pinfunction "S12_P$3") (pintype "bidirectional"))
    )
    (net (code "29") (name "GND_HOST") (class "Default")
      (node (ref "ACSL6410") (pin "P$1") (pinfunction "P$1_P$1") (pintype "bidirectional"))
      (node (ref "ACSL6410") (pin "P$5") (pinfunction "P$5_P$5") (pintype "bidirectional"))
      (node (ref "ACSL6410") (pin "P$7") (pinfunction "P$7_P$7") (pintype "bidirectional"))
      (node (ref "C4") (pin "2") (pinfunction "2_2") (pintype "passive"))
      (node (ref "C5") (pin "2") (pinfunction "2_2") (pintype "passive"))
      (node (ref "LTC1693") (pin "P$2") (pinfunction "GND1_P$2") (pintype "bidirectional"))
      (node (ref "LTC1693") (pin "P$4") (pinfunction "GND2_P$4") (pintype "bidirectional"))
      (node (ref "MODICE") (pin "GND_IN") (pinfunction "GND_IN_GND_IN") (pintype "bidirectional"))
      (node (ref "MODICE") (pin "GND_OUT") (pinfunction "GND_OUT_GND_OUT") (pintype "bidirectional"))
      (node (ref "R11") (pin "2") (pinfunction "2_2") (pintype "passive"))
    )
    (net (code "30") (name "Net-(ACSL6410-PadP$4)") (class "Default")
      (node (ref "ACSL6410") (pin "P$4") (pinfunction "P$4_P$4") (pintype "bidirectional"))
      (node (ref "R9") (pin "1") (pinfunction "1_1") (pintype "passive"))
    )
    (net (code "31") (name "Net-(ACSL6410-PadP$6)") (class "Default")
      (node (ref "ACSL6410") (pin "P$6") (pinfunction "P$6_P$6") (pintype "bidirectional"))
      (node (ref "R8") (pin "1") (pinfunction "1_1") (pintype "passive"))
    )
    (net (code "32") (name "Net-(ACSL6410-PadP$8)") (class "Default")
      (node (ref "ACSL6410") (pin "P$8") (pinfunction "P$8_P$8") (pintype "bidirectional"))
      (node (ref "R4") (pin "1") (pinfunction "1_1") (pintype "passive"))
    )
    (net (code "33") (name "Net-(ACSL6410-PadP$10)") (class "Default")
      (node (ref "ACSL6410") (pin "P$10") (pinfunction "P$10_P$10") (pintype "bidirectional"))
      (node (ref "ACSL6410") (pin "P$15") (pinfunction "P$15_P$15") (pintype "bidirectional"))
      (node (ref "BAT1") (pin "2") (pinfunction "2_2") (pintype "passive"))
      (node (ref "BAT2") (pin "2") (pinfunction "2_2") (pintype "passive"))
      (node (ref "C1") (pin "2") (pinfunction "2_2") (pintype "passive"))
      (node (ref "C2") (pin "1") (pinfunction "1_1") (pintype "passive"))
    )
    (net (code "34") (name "Net-(ACSL6410-PadP$16)") (class "Default")
      (node (ref "ACSL6410") (pin "P$16") (pinfunction "P$16_P$16") (pintype "bidirectional"))
      (node (ref "R13") (pin "1") (pinfunction "1_1") (pintype "passive"))
    )
    (net (code "35") (name "Net-(BAT1-Pad3)") (class "Default")
      (node (ref "BAT1") (pin "3") (pinfunction "3_3") (pintype "passive"))
      (node (ref "PE68386") (pin "4") (pinfunction "4_4") (pintype "bidirectional"))
    )
    (net (code "36") (name "Net-(BAT2-Pad3)") (class "Default")
      (node (ref "BAT2") (pin "3") (pinfunction "3_3") (pintype "passive"))
      (node (ref "PE68386") (pin "6") (pinfunction "6_6") (pintype "bidirectional"))
    )
    (net (code "37") (name "Net-(C3-Pad1)") (class "Default")
      (node (ref "C3") (pin "1") (pinfunction "1_1") (pintype "passive"))
      (node (ref "PE68386") (pin "1") (pinfunction "1_1") (pintype "bidirectional"))
    )
    (net (code "38") (name "Net-(CELL12-Pad1)") (class "Default")
      (node (ref "CELL12") (pin "1") (pinfunction "1_1") (pintype "passive"))
      (node (ref "L1") (pin "1") (pinfunction "1_1") (pintype "passive"))
      (node (ref "MODICE") (pin "C12") (pinfunction "C12_C12") (pintype "bidirectional"))
    )
    (net (code "39") (name "Net-(CSBI-P$3)") (class "Default")
      (node (ref "CSBI") (pin "3") (pinfunction "P$3_3") (pintype "bidirectional"))
      (node (ref "R4") (pin "2") (pinfunction "2_2") (pintype "passive"))
    )
    (net (code "40") (name "Net-(LED1-PadP$1)") (class "Default")
      (node (ref "LED1") (pin "P$1") (pinfunction "P$1_P$1") (pintype "passive"))
      (node (ref "R24") (pin "1") (pinfunction "1_1") (pintype "passive"))
    )
    (net (code "41") (name "Net-(LED2-PadP$1)") (class "Default")
      (node (ref "LED2") (pin "P$1") (pinfunction "P$1_P$1") (pintype "passive"))
      (node (ref "R29") (pin "1") (pinfunction "1_1") (pintype "passive"))
    )
    (net (code "42") (name "Net-(LED3-PadP$1)") (class "Default")
      (node (ref "LED3") (pin "P$1") (pinfunction "P$1_P$1") (pintype "passive"))
      (node (ref "R34") (pin "1") (pinfunction "1_1") (pintype "passive"))
    )
    (net (code "43") (name "Net-(LED4-PadP$1)") (class "Default")
      (node (ref "LED4") (pin "P$1") (pinfunction "P$1_P$1") (pintype "passive"))
      (node (ref "R39") (pin "1") (pinfunction "1_1") (pintype "passive"))
    )
    (net (code "44") (name "Net-(LED5-PadP$1)") (class "Default")
      (node (ref "LED5") (pin "P$1") (pinfunction "P$1_P$1") (pintype "passive"))
      (node (ref "R44") (pin "1") (pinfunction "1_1") (pintype "passive"))
    )
    (net (code "45") (name "Net-(LED6-PadP$1)") (class "Default")
      (node (ref "LED6") (pin "P$1") (pinfunction "P$1_P$1") (pintype "passive"))
      (node (ref "R49") (pin "1") (pinfunction "1_1") (pintype "passive"))
    )
    (net (code "46") (name "Net-(LED7-PadP$1)") (class "Default")
      (node (ref "LED7") (pin "P$1") (pinfunction "P$1_P$1") (pintype "passive"))
      (node (ref "R54") (pin "1") (pinfunction "1_1") (pintype "passive"))
    )
    (net (code "47") (name "Net-(LED8-PadP$1)") (class "Default")
      (node (ref "LED8") (pin "P$1") (pinfunction "P$1_P$1") (pintype "passive"))
      (node (ref "R59") (pin "1") (pinfunction "1_1") (pintype "passive"))
    )
    (net (code "48") (name "Net-(LED9-PadP$1)") (class "Default")
      (node (ref "LED9") (pin "P$1") (pinfunction "P$1_P$1") (pintype "passive"))
      (node (ref "R64") (pin "1") (pinfunction "1_1") (pintype "passive"))
    )
    (net (code "49") (name "Net-(LED10-PadP$1)") (class "Default")
      (node (ref "LED10") (pin "P$1") (pinfunction "P$1_P$1") (pintype "passive"))
      (node (ref "R69") (pin "1") (pinfunction "1_1") (pintype "passive"))
    )
    (net (code "50") (name "Net-(LED11-PadP$1)") (class "Default")
      (node (ref "LED11") (pin "P$1") (pinfunction "P$1_P$1") (pintype "passive"))
      (node (ref "R74") (pin "1") (pinfunction "1_1") (pintype "passive"))
    )
    (net (code "51") (name "Net-(LED12-PadP$1)") (class "Default")
      (node (ref "LED12") (pin "P$1") (pinfunction "P$1_P$1") (pintype "passive"))
      (node (ref "R79") (pin "1") (pinfunction "1_1") (pintype "passive"))
    )
    (net (code "52") (name "Net-(LTC1693-IN1)") (class "Default")
      (node (ref "C5") (pin "1") (pinfunction "1_1") (pintype "passive"))
      (node (ref "LTC1693") (pin "P$1") (pinfunction "IN1_P$1") (pintype "bidirectional"))
      (node (ref "R11") (pin "1") (pinfunction "1_1") (pintype "passive"))
      (node (ref "R12") (pin "2") (pinfunction "2_2") (pintype "passive"))
    )
    (net (code "53") (name "Net-(LTC1693-IN2)") (class "Default")
      (node (ref "C3") (pin "2") (pinfunction "2_2") (pintype "passive"))
      (node (ref "LTC1693") (pin "P$3") (pinfunction "IN2_P$3") (pintype "bidirectional"))
      (node (ref "LTC1693") (pin "P$7") (pinfunction "OUT1_P$7") (pintype "bidirectional"))
    )
    (net (code "54") (name "Net-(LTC1693-OUT2)") (class "Default")
      (node (ref "LTC1693") (pin "P$5") (pinfunction "OUT2_P$5") (pintype "bidirectional"))
      (node (ref "PE68386") (pin "3") (pinfunction "3_3") (pintype "bidirectional"))
      (node (ref "R12") (pin "1") (pinfunction "1_1") (pintype "passive"))
    )
    (net (code "55") (name "Net-(R22-Pad2)") (class "Default")
      (node (ref "R22") (pin "2") (pinfunction "2_2") (pintype "passive"))
      (node (ref "R23") (pin "1") (pinfunction "1_1") (pintype "passive"))
    )
    (net (code "56") (name "Net-(R27-Pad2)") (class "Default")
      (node (ref "R27") (pin "2") (pinfunction "2_2") (pintype "passive"))
      (node (ref "R28") (pin "1") (pinfunction "1_1") (pintype "passive"))
    )
    (net (code "57") (name "Net-(R32-Pad2)") (class "Default")
      (node (ref "R32") (pin "2") (pinfunction "2_2") (pintype "passive"))
      (node (ref "R33") (pin "1") (pinfunction "1_1") (pintype "passive"))
    )
    (net (code "58") (name "Net-(R37-Pad2)") (class "Default")
      (node (ref "R37") (pin "2") (pinfunction "2_2") (pintype "passive"))
      (node (ref "R38") (pin "1") (pinfunction "1_1") (pintype "passive"))
    )
    (net (code "59") (name "Net-(R42-Pad2)") (class "Default")
      (node (ref "R42") (pin "2") (pinfunction "2_2") (pintype "passive"))
      (node (ref "R43") (pin "1") (pinfunction "1_1") (pintype "passive"))
    )
    (net (code "60") (name "Net-(R47-Pad2)") (class "Default")
      (node (ref "R47") (pin "2") (pinfunction "2_2") (pintype "passive"))
      (node (ref "R48") (pin "1") (pinfunction "1_1") (pintype "passive"))
    )
    (net (code "61") (name "Net-(R52-Pad2)") (class "Default")
      (node (ref "R52") (pin "2") (pinfunction "2_2") (pintype "passive"))
      (node (ref "R53") (pin "1") (pinfunction "1_1") (pintype "passive"))
    )
    (net (code "62") (name "Net-(R57-Pad2)") (class "Default")
      (node (ref "R57") (pin "2") (pinfunction "2_2") (pintype "passive"))
      (node (ref "R58") (pin "1") (pinfunction "1_1") (pintype "passive"))
    )
    (net (code "63") (name "Net-(R62-Pad2)") (class "Default")
      (node (ref "R62") (pin "2") (pinfunction "2_2") (pintype "passive"))
      (node (ref "R63") (pin "1") (pinfunction "1_1") (pintype "passive"))
    )
    (net (code "64") (name "Net-(R67-Pad2)") (class "Default")
      (node (ref "R67") (pin "2") (pinfunction "2_2") (pintype "passive"))
      (node (ref "R68") (pin "1") (pinfunction "1_1") (pintype "passive"))
    )
    (net (code "65") (name "Net-(R72-Pad2)") (class "Default")
      (node (ref "R72") (pin "2") (pinfunction "2_2") (pintype "passive"))
      (node (ref "R73") (pin "1") (pinfunction "1_1") (pintype "passive"))
    )
    (net (code "66") (name "Net-(R77-Pad2)") (class "Default")
      (node (ref "R77") (pin "2") (pinfunction "2_2") (pintype "passive"))
      (node (ref "R78") (pin "1") (pinfunction "1_1") (pintype "passive"))
    )
    (net (code "67") (name "Net-(SCKI-P$3)") (class "Default")
      (node (ref "R9") (pin "2") (pinfunction "2_2") (pintype "passive"))
      (node (ref "SCKI") (pin "3") (pinfunction "P$3_3") (pintype "bidirectional"))
    )
    (net (code "68") (name "Net-(SDI-P$3)") (class "Default")
      (node (ref "R8") (pin "2") (pinfunction "2_2") (pintype "passive"))
      (node (ref "SDI") (pin "3") (pinfunction "P$3_3") (pintype "bidirectional"))
    )
    (net (code "69") (name "Net-(T1-P$1)") (class "Default")
      (node (ref "R21") (pin "1") (pinfunction "1_1") (pintype "passive"))
      (node (ref "T1") (pin "1") (pinfunction "P$1_1") (pintype "passive"))
    )
    (net (code "70") (name "Net-(T1-P$2)") (class "Default")
      (node (ref "MODICE") (pin "C1") (pinfunction "C1_C1") (pintype "bidirectional"))
      (node (ref "R20") (pin "1") (pinfunction "1_1") (pintype "passive"))
      (node (ref "R27") (pin "1") (pinfunction "1_1") (pintype "passive"))
      (node (ref "R29") (pin "2") (pinfunction "2_2") (pintype "passive"))
      (node (ref "T1") (pin "2") (pinfunction "P$2_2") (pintype "passive"))
    )
    (net (code "71") (name "Net-(T1-P$3)") (class "Default")
      (node (ref "LED1") (pin "P$2") (pinfunction "P$2_P$2") (pintype "passive"))
      (node (ref "R23") (pin "2") (pinfunction "2_2") (pintype "passive"))
      (node (ref "T1") (pin "3") (pinfunction "P$3_3") (pintype "passive"))
    )
    (net (code "72") (name "Net-(T2-P$1)") (class "Default")
      (node (ref "R26") (pin "1") (pinfunction "1_1") (pintype "passive"))
      (node (ref "T2") (pin "1") (pinfunction "P$1_1") (pintype "passive"))
    )
    (net (code "73") (name "Net-(T2-P$2)") (class "Default")
      (node (ref "MODICE") (pin "C2") (pinfunction "C2_C2") (pintype "bidirectional"))
      (node (ref "R25") (pin "1") (pinfunction "1_1") (pintype "passive"))
      (node (ref "R32") (pin "1") (pinfunction "1_1") (pintype "passive"))
      (node (ref "R34") (pin "2") (pinfunction "2_2") (pintype "passive"))
      (node (ref "T2") (pin "2") (pinfunction "P$2_2") (pintype "passive"))
    )
    (net (code "74") (name "Net-(T2-P$3)") (class "Default")
      (node (ref "LED2") (pin "P$2") (pinfunction "P$2_P$2") (pintype "passive"))
      (node (ref "R28") (pin "2") (pinfunction "2_2") (pintype "passive"))
      (node (ref "T2") (pin "3") (pinfunction "P$3_3") (pintype "passive"))
    )
    (net (code "75") (name "Net-(T3-P$1)") (class "Default")
      (node (ref "R31") (pin "1") (pinfunction "1_1") (pintype "passive"))
      (node (ref "T3") (pin "1") (pinfunction "P$1_1") (pintype "passive"))
    )
    (net (code "76") (name "Net-(T3-P$2)") (class "Default")
      (node (ref "MODICE") (pin "C3") (pinfunction "C3_C3") (pintype "bidirectional"))
      (node (ref "R30") (pin "1") (pinfunction "1_1") (pintype "passive"))
      (node (ref "R37") (pin "1") (pinfunction "1_1") (pintype "passive"))
      (node (ref "R39") (pin "2") (pinfunction "2_2") (pintype "passive"))
      (node (ref "T3") (pin "2") (pinfunction "P$2_2") (pintype "passive"))
    )
    (net (code "77") (name "Net-(T3-P$3)") (class "Default")
      (node (ref "LED3") (pin "P$2") (pinfunction "P$2_P$2") (pintype "passive"))
      (node (ref "R33") (pin "2") (pinfunction "2_2") (pintype "passive"))
      (node (ref "T3") (pin "3") (pinfunction "P$3_3") (pintype "passive"))
    )
    (net (code "78") (name "Net-(T4-P$1)") (class "Default")
      (node (ref "R36") (pin "1") (pinfunction "1_1") (pintype "passive"))
      (node (ref "T4") (pin "1") (pinfunction "P$1_1") (pintype "passive"))
    )
    (net (code "79") (name "Net-(T4-P$2)") (class "Default")
      (node (ref "CELL5") (pin "2") (pinfunction "2_2") (pintype "passive"))
      (node (ref "MODICE") (pin "C4") (pinfunction "C4_C4") (pintype "bidirectional"))
      (node (ref "R35") (pin "1") (pinfunction "1_1") (pintype "passive"))
      (node (ref "R42") (pin "1") (pinfunction "1_1") (pintype "passive"))
      (node (ref "R44") (pin "2") (pinfunction "2_2") (pintype "passive"))
      (node (ref "T4") (pin "2") (pinfunction "P$2_2") (pintype "passive"))
    )
    (net (code "80") (name "Net-(T4-P$3)") (class "Default")
      (node (ref "LED4") (pin "P$2") (pinfunction "P$2_P$2") (pintype "passive"))
      (node (ref "R38") (pin "2") (pinfunction "2_2") (pintype "passive"))
      (node (ref "T4") (pin "3") (pinfunction "P$3_3") (pintype "passive"))
    )
    (net (code "81") (name "Net-(T5-P$1)") (class "Default")
      (node (ref "R41") (pin "1") (pinfunction "1_1") (pintype "passive"))
      (node (ref "T5") (pin "1") (pinfunction "P$1_1") (pintype "passive"))
    )
    (net (code "82") (name "Net-(T5-P$2)") (class "Default")
      (node (ref "CELL5") (pin "1") (pinfunction "1_1") (pintype "passive"))
      (node (ref "CELL6") (pin "2") (pinfunction "2_2") (pintype "passive"))
      (node (ref "MODICE") (pin "C5") (pinfunction "C5_C5") (pintype "bidirectional"))
      (node (ref "R40") (pin "1") (pinfunction "1_1") (pintype "passive"))
      (node (ref "R47") (pin "1") (pinfunction "1_1") (pintype "passive"))
      (node (ref "R49") (pin "2") (pinfunction "2_2") (pintype "passive"))
      (node (ref "T5") (pin "2") (pinfunction "P$2_2") (pintype "passive"))
    )
    (net (code "83") (name "Net-(T5-P$3)") (class "Default")
      (node (ref "LED5") (pin "P$2") (pinfunction "P$2_P$2") (pintype "passive"))
      (node (ref "R43") (pin "2") (pinfunction "2_2") (pintype "passive"))
      (node (ref "T5") (pin "3") (pinfunction "P$3_3") (pintype "passive"))
    )
    (net (code "84") (name "Net-(T6-P$1)") (class "Default")
      (node (ref "R46") (pin "1") (pinfunction "1_1") (pintype "passive"))
      (node (ref "T6") (pin "1") (pinfunction "P$1_1") (pintype "passive"))
    )
    (net (code "85") (name "Net-(T6-P$2)") (class "Default")
      (node (ref "CELL6") (pin "1") (pinfunction "1_1") (pintype "passive"))
      (node (ref "CELL7") (pin "2") (pinfunction "2_2") (pintype "passive"))
      (node (ref "MODICE") (pin "C6") (pinfunction "C6_C6") (pintype "bidirectional"))
      (node (ref "R45") (pin "1") (pinfunction "1_1") (pintype "passive"))
      (node (ref "R52") (pin "1") (pinfunction "1_1") (pintype "passive"))
      (node (ref "R54") (pin "2") (pinfunction "2_2") (pintype "passive"))
      (node (ref "T6") (pin "2") (pinfunction "P$2_2") (pintype "passive"))
    )
    (net (code "86") (name "Net-(T6-P$3)") (class "Default")
      (node (ref "LED6") (pin "P$2") (pinfunction "P$2_P$2") (pintype "passive"))
      (node (ref "R48") (pin "2") (pinfunction "2_2") (pintype "passive"))
      (node (ref "T6") (pin "3") (pinfunction "P$3_3") (pintype "passive"))
    )
    (net (code "87") (name "Net-(T7-P$1)") (class "Default")
      (node (ref "R51") (pin "1") (pinfunction "1_1") (pintype "passive"))
      (node (ref "T7") (pin "1") (pinfunction "P$1_1") (pintype "passive"))
    )
    (net (code "88") (name "Net-(T7-P$2)") (class "Default")
      (node (ref "CELL7") (pin "1") (pinfunction "1_1") (pintype "passive"))
      (node (ref "CELL8") (pin "2") (pinfunction "2_2") (pintype "passive"))
      (node (ref "MODICE") (pin "C7") (pinfunction "C7_C7") (pintype "bidirectional"))
      (node (ref "R50") (pin "1") (pinfunction "1_1") (pintype "passive"))
      (node (ref "R57") (pin "1") (pinfunction "1_1") (pintype "passive"))
      (node (ref "R59") (pin "2") (pinfunction "2_2") (pintype "passive"))
      (node (ref "T7") (pin "2") (pinfunction "P$2_2") (pintype "passive"))
    )
    (net (code "89") (name "Net-(T7-P$3)") (class "Default")
      (node (ref "LED7") (pin "P$2") (pinfunction "P$2_P$2") (pintype "passive"))
      (node (ref "R53") (pin "2") (pinfunction "2_2") (pintype "passive"))
      (node (ref "T7") (pin "3") (pinfunction "P$3_3") (pintype "passive"))
    )
    (net (code "90") (name "Net-(T8-P$1)") (class "Default")
      (node (ref "R56") (pin "1") (pinfunction "1_1") (pintype "passive"))
      (node (ref "T8") (pin "1") (pinfunction "P$1_1") (pintype "passive"))
    )
    (net (code "91") (name "Net-(T8-P$2)") (class "Default")
      (node (ref "CELL8") (pin "1") (pinfunction "1_1") (pintype "passive"))
      (node (ref "CELL9") (pin "2") (pinfunction "2_2") (pintype "passive"))
      (node (ref "MODICE") (pin "C8") (pinfunction "C8_C8") (pintype "bidirectional"))
      (node (ref "R55") (pin "1") (pinfunction "1_1") (pintype "passive"))
      (node (ref "R62") (pin "1") (pinfunction "1_1") (pintype "passive"))
      (node (ref "R64") (pin "2") (pinfunction "2_2") (pintype "passive"))
      (node (ref "T8") (pin "2") (pinfunction "P$2_2") (pintype "passive"))
    )
    (net (code "92") (name "Net-(T8-P$3)") (class "Default")
      (node (ref "LED8") (pin "P$2") (pinfunction "P$2_P$2") (pintype "passive"))
      (node (ref "R58") (pin "2") (pinfunction "2_2") (pintype "passive"))
      (node (ref "T8") (pin "3") (pinfunction "P$3_3") (pintype "passive"))
    )
    (net (code "93") (name "Net-(T9-P$1)") (class "Default")
      (node (ref "R61") (pin "1") (pinfunction "1_1") (pintype "passive"))
      (node (ref "T9") (pin "1") (pinfunction "P$1_1") (pintype "passive"))
    )
    (net (code "94") (name "Net-(T9-P$2)") (class "Default")
      (node (ref "CELL10") (pin "2") (pinfunction "2_2") (pintype "passive"))
      (node (ref "CELL9") (pin "1") (pinfunction "1_1") (pintype "passive"))
      (node (ref "MODICE") (pin "C9") (pinfunction "C9_C9") (pintype "bidirectional"))
      (node (ref "R60") (pin "1") (pinfunction "1_1") (pintype "passive"))
      (node (ref "R67") (pin "1") (pinfunction "1_1") (pintype "passive"))
      (node (ref "R69") (pin "2") (pinfunction "2_2") (pintype "passive"))
      (node (ref "T9") (pin "2") (pinfunction "P$2_2") (pintype "passive"))
    )
    (net (code "95") (name "Net-(T9-P$3)") (class "Default")
      (node (ref "LED9") (pin "P$2") (pinfunction "P$2_P$2") (pintype "passive"))
      (node (ref "R63") (pin "2") (pinfunction "2_2") (pintype "passive"))
      (node (ref "T9") (pin "3") (pinfunction "P$3_3") (pintype "passive"))
    )
    (net (code "96") (name "Net-(T10-P$1)") (class "Default")
      (node (ref "R66") (pin "1") (pinfunction "1_1") (pintype "passive"))
      (node (ref "T10") (pin "1") (pinfunction "P$1_1") (pintype "passive"))
    )
    (net (code "97") (name "Net-(T10-P$2)") (class "Default")
      (node (ref "CELL10") (pin "1") (pinfunction "1_1") (pintype "passive"))
      (node (ref "CELL11") (pin "2") (pinfunction "2_2") (pintype "passive"))
      (node (ref "MODICE") (pin "C10") (pinfunction "C10_C10") (pintype "bidirectional"))
      (node (ref "R65") (pin "1") (pinfunction "1_1") (pintype "passive"))
      (node (ref "R72") (pin "1") (pinfunction "1_1") (pintype "passive"))
      (node (ref "R74") (pin "2") (pinfunction "2_2") (pintype "passive"))
      (node (ref "T10") (pin "2") (pinfunction "P$2_2") (pintype "passive"))
    )
    (net (code "98") (name "Net-(T10-P$3)") (class "Default")
      (node (ref "LED10") (pin "P$2") (pinfunction "P$2_P$2") (pintype "passive"))
      (node (ref "R68") (pin "2") (pinfunction "2_2") (pintype "passive"))
      (node (ref "T10") (pin "3") (pinfunction "P$3_3") (pintype "passive"))
    )
    (net (code "99") (name "Net-(T11-P$1)") (class "Default")
      (node (ref "R71") (pin "1") (pinfunction "1_1") (pintype "passive"))
      (node (ref "T11") (pin "1") (pinfunction "P$1_1") (pintype "passive"))
    )
    (net (code "100") (name "Net-(T11-P$2)") (class "Default")
      (node (ref "CELL11") (pin "1") (pinfunction "1_1") (pintype "passive"))
      (node (ref "CELL12") (pin "2") (pinfunction "2_2") (pintype "passive"))
      (node (ref "MODICE") (pin "C11") (pinfunction "C11_C11") (pintype "bidirectional"))
      (node (ref "R70") (pin "1") (pinfunction "1_1") (pintype "passive"))
      (node (ref "R77") (pin "1") (pinfunction "1_1") (pintype "passive"))
      (node (ref "R79") (pin "2") (pinfunction "2_2") (pintype "passive"))
      (node (ref "T11") (pin "2") (pinfunction "P$2_2") (pintype "passive"))
    )
    (net (code "101") (name "Net-(T11-P$3)") (class "Default")
      (node (ref "LED11") (pin "P$2") (pinfunction "P$2_P$2") (pintype "passive"))
      (node (ref "R73") (pin "2") (pinfunction "2_2") (pintype "passive"))
      (node (ref "T11") (pin "3") (pinfunction "P$3_3") (pintype "passive"))
    )
    (net (code "102") (name "Net-(T12-P$1)") (class "Default")
      (node (ref "R76") (pin "1") (pinfunction "1_1") (pintype "passive"))
      (node (ref "T12") (pin "1") (pinfunction "P$1_1") (pintype "passive"))
    )
    (net (code "103") (name "Net-(T12-P$3)") (class "Default")
      (node (ref "LED12") (pin "P$2") (pinfunction "P$2_P$2") (pintype "passive"))
      (node (ref "R78") (pin "2") (pinfunction "2_2") (pintype "passive"))
      (node (ref "T12") (pin "3") (pinfunction "P$3_3") (pintype "passive"))
    )
    (net (code "104") (name "Net-(X-BMS-A0)") (class "Default")
      (node (ref "A0") (pin "2") (pinfunction "2_2") (pintype "passive"))
      (node (ref "X-BMS") (pin "P$37") (pinfunction "A0_P$37") (pintype "bidirectional"))
    )
    (net (code "105") (name "Net-(X-BMS-A1)") (class "Default")
      (node (ref "A1") (pin "2") (pinfunction "2_2") (pintype "passive"))
      (node (ref "X-BMS") (pin "P$38") (pinfunction "A1_P$38") (pintype "bidirectional"))
    )
    (net (code "106") (name "Net-(X-BMS-A2)") (class "Default")
      (node (ref "A2") (pin "2") (pinfunction "2_2") (pintype "passive"))
      (node (ref "X-BMS") (pin "P$39") (pinfunction "A2_P$39") (pintype "bidirectional"))
    )
    (net (code "107") (name "Net-(X-BMS-A3)") (class "Default")
      (node (ref "A3") (pin "2") (pinfunction "2_2") (pintype "passive"))
      (node (ref "X-BMS") (pin "P$40") (pinfunction "A3_P$40") (pintype "bidirectional"))
    )
    (net (code "108") (name "Net-(X-BMS-CSBI)") (class "Default")
      (node (ref "ACSL6410") (pin "P$11") (pinfunction "P$11_P$11") (pintype "bidirectional"))
      (node (ref "R1") (pin "1") (pinfunction "1_1") (pintype "passive"))
      (node (ref "X-BMS") (pin "P$44") (pinfunction "CSBI_P$44") (pintype "bidirectional"))
    )
    (net (code "109") (name "Net-(X-BMS-MMB)") (class "Default")
      (node (ref "R16") (pin "1") (pinfunction "1_1") (pintype "passive"))
      (node (ref "X-BMS") (pin "P$33") (pinfunction "MMB_P$33") (pintype "bidirectional"))
    )
    (net (code "110") (name "Net-(X-BMS-SCKI)") (class "Default")
      (node (ref "ACSL6410") (pin "P$13") (pinfunction "P$13_P$13") (pintype "bidirectional"))
      (node (ref "R3") (pin "1") (pinfunction "1_1") (pintype "passive"))
      (node (ref "X-BMS") (pin "P$41") (pinfunction "SCKI_P$41") (pintype "bidirectional"))
    )
    (net (code "111") (name "Net-(X-BMS-SDI)") (class "Default")
      (node (ref "ACSL6410") (pin "P$12") (pinfunction "P$12_P$12") (pintype "bidirectional"))
      (node (ref "R2") (pin "1") (pinfunction "1_1") (pintype "passive"))
      (node (ref "X-BMS") (pin "P$42") (pinfunction "SDI_P$42") (pintype "bidirectional"))
    )
    (net (code "112") (name "Net-(X-BMS-SDO)") (class "Default")
      (node (ref "R13") (pin "2") (pinfunction "2_2") (pintype "passive"))
      (node (ref "X-BMS") (pin "P$43") (pinfunction "SDO_P$43") (pintype "bidirectional"))
    )
    (net (code "113") (name "Net-(X-BMS-V_REF)") (class "Default")
      (node (ref "C7") (pin "2") (pinfunction "2_2") (pintype "passive"))
      (node (ref "R14") (pin "2") (pinfunction "2_2") (pintype "passive"))
      (node (ref "R15") (pin "2") (pinfunction "2_2") (pintype "passive"))
      (node (ref "X-BMS") (pin "P$30") (pinfunction "V_REF_P$30") (pintype "bidirectional"))
    )
    (net (code "114") (name "Net-(X-BMS-WDTB)") (class "Default")
      (node (ref "R17") (pin "1") (pinfunction "1_1") (pintype "passive"))
      (node (ref "X-BMS") (pin "P$34") (pinfunction "WDTB_P$34") (pintype "bidirectional"))
    )
    (net (code "115") (name "SCKI") (class "Default")
      (node (ref "MODICE") (pin "SCKI1") (pinfunction "SCKI1_SCKI1") (pintype "bidirectional"))
      (node (ref "MODICE") (pin "SCKI2") (pinfunction "SCKI2_SCKI2") (pintype "bidirectional"))
      (node (ref "R7") (pin "2") (pinfunction "2_2") (pintype "passive"))
      (node (ref "SCKI") (pin "1") (pinfunction "P$1_1") (pintype "bidirectional"))
    )
    (net (code "116") (name "SDI") (class "Default")
      (node (ref "MODICE") (pin "SDI1") (pinfunction "SDI1_SDI1") (pintype "bidirectional"))
      (node (ref "MODICE") (pin "SDI2") (pinfunction "SDI2_SDI2") (pintype "bidirectional"))
      (node (ref "R6") (pin "2") (pinfunction "2_2") (pintype "passive"))
      (node (ref "SDI") (pin "1") (pinfunction "P$1_1") (pintype "bidirectional"))
    )
    (net (code "117") (name "SDO") (class "Default")
      (node (ref "ACSL6410") (pin "P$2") (pinfunction "P$2_P$2") (pintype "bidirectional"))
      (node (ref "MODICE") (pin "SDO1") (pinfunction "SDO1_SDO1") (pintype "bidirectional"))
      (node (ref "MODICE") (pin "SDO2") (pinfunction "SDO2_SDO2") (pintype "bidirectional"))
      (node (ref "R10") (pin "2") (pinfunction "2_2") (pintype "passive"))
    )
    (net (code "118") (name "V_REG") (class "Default")
      (node (ref "A0") (pin "1") (pinfunction "1_1") (pintype "passive"))
      (node (ref "A1") (pin "1") (pinfunction "1_1") (pintype "passive"))
      (node (ref "A2") (pin "1") (pinfunction "1_1") (pintype "passive"))
      (node (ref "A3") (pin "1") (pinfunction "1_1") (pintype "passive"))
      (node (ref "C6") (pin "1") (pinfunction "1_1") (pintype "passive"))
      (node (ref "R1") (pin "2") (pinfunction "2_2") (pintype "passive"))
      (node (ref "R16") (pin "2") (pinfunction "2_2") (pintype "passive"))
      (node (ref "R17") (pin "2") (pinfunction "2_2") (pintype "passive"))
      (node (ref "R2") (pin "2") (pinfunction "2_2") (pintype "passive"))
      (node (ref "R3") (pin "2") (pinfunction "2_2") (pintype "passive"))
      (node (ref "X-BMS") (pin "P$31") (pinfunction "V_REG_P$31") (pintype "bidirectional"))
    )
    (net (code "119") (name "V_TEMP1") (class "Default")
      (node (ref "C9") (pin "1") (pinfunction "1_1") (pintype "passive"))
      (node (ref "MODICE") (pin "TEMP1") (pinfunction "TEMP1_TEMP1") (pintype "bidirectional"))
      (node (ref "R15") (pin "1") (pinfunction "1_1") (pintype "passive"))
      (node (ref "X-BMS") (pin "P$28") (pinfunction "V_TEMP1_P$28") (pintype "bidirectional"))
    )
    (net (code "120") (name "V_TEMP2") (class "Default")
      (node (ref "C8") (pin "1") (pinfunction "1_1") (pintype "passive"))
      (node (ref "MODICE") (pin "TEMP2") (pinfunction "TEMP2_TEMP2") (pintype "bidirectional"))
      (node (ref "R14") (pin "1") (pinfunction "1_1") (pintype "passive"))
      (node (ref "X-BMS") (pin "P$29") (pinfunction "V-TEMP2_P$29") (pintype "bidirectional"))
    )
    (net (code "121") (name "unconnected-(MODICE-NC1-PadNC)") (class "Default")
      (node (ref "MODICE") (pin "NC") (pinfunction "NC1_NC") (pintype "bidirectional"))
    )
    (net (code "122") (name "unconnected-(MODICE-NC2-PadNC1)") (class "Default")
      (node (ref "MODICE") (pin "NC1") (pinfunction "NC2_NC1") (pintype "bidirectional"))
    )
    (net (code "123") (name "unconnected-(MODICE-NC3-PadNC2)") (class "Default")
      (node (ref "MODICE") (pin "NC2") (pinfunction "NC3_NC2") (pintype "bidirectional"))
    )
    (net (code "124") (name "unconnected-(X-BMS-GPIO1-PadP$35)") (class "Default")
      (node (ref "X-BMS") (pin "P$35") (pinfunction "GPIO1_P$35") (pintype "bidirectional"))
    )
    (net (code "125") (name "unconnected-(X-BMS-GPIO2-PadP$36)") (class "Default")
      (node (ref "X-BMS") (pin "P$36") (pinfunction "GPIO2_P$36") (pintype "bidirectional"))
    )
  )
)
